# 14-TestFixture.net
KiCad netlist of a schematic drawn in Altium Designer
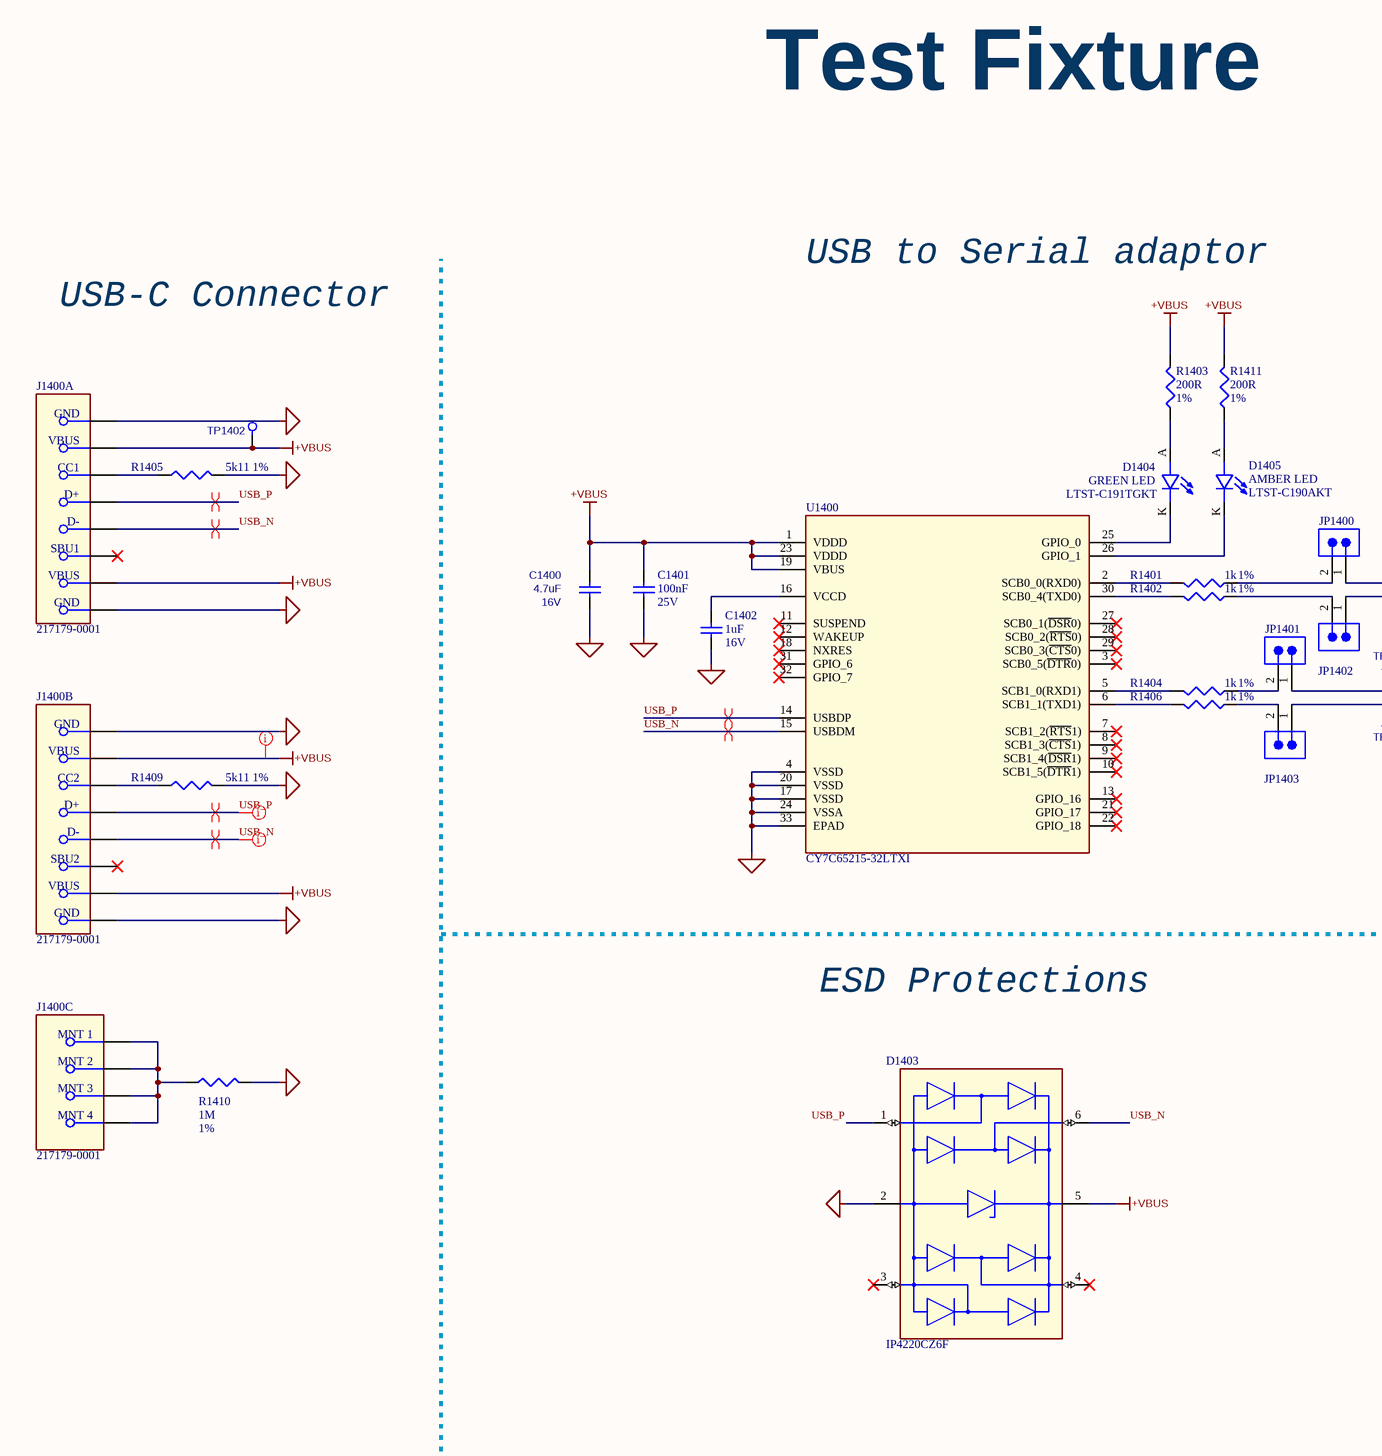
[diagram p0: 14-TestFixture.SchDoc, left]
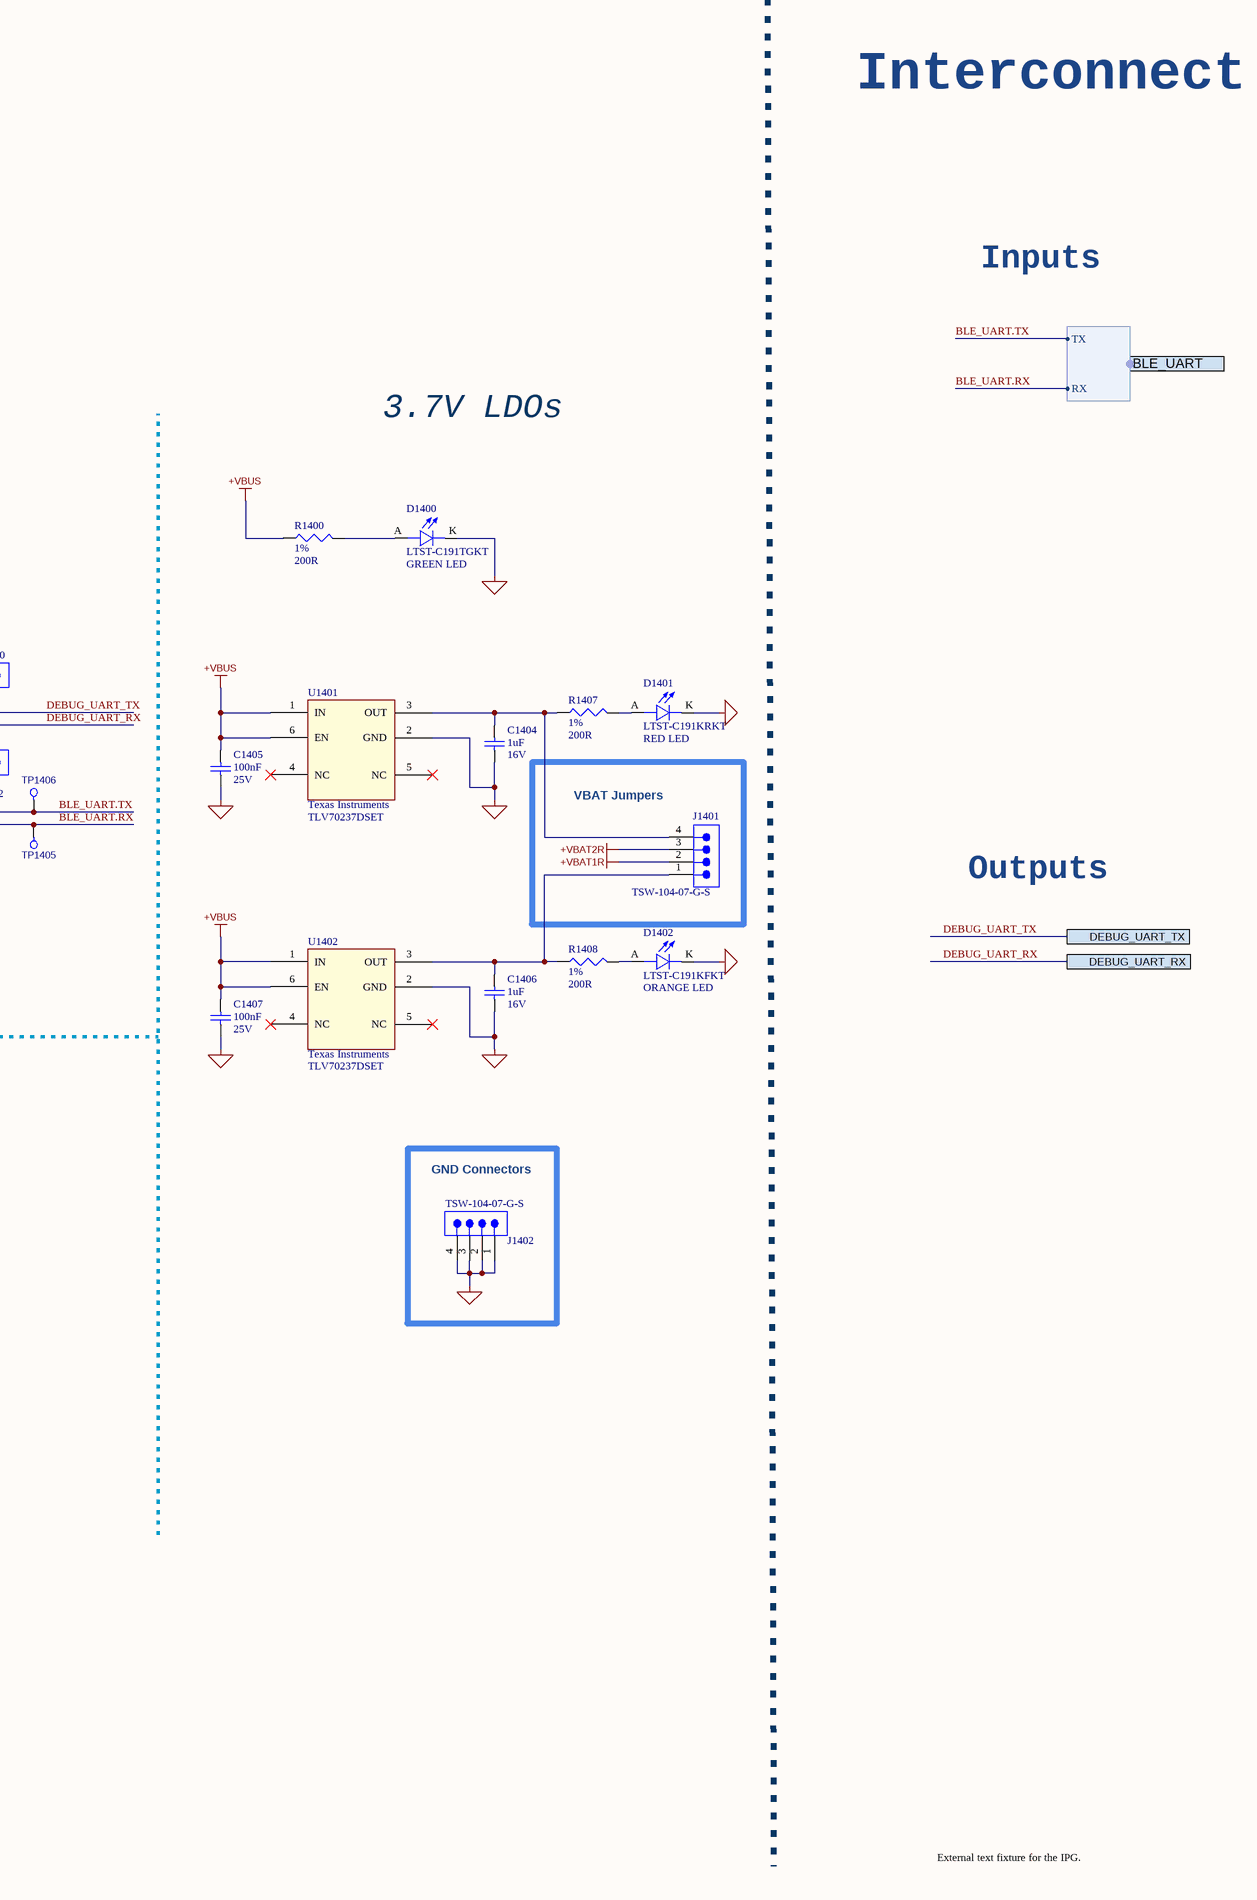
[diagram p1: 14-TestFixture.SchDoc, right]

(export (version "E")
  (design (tool "Eeschema 10.0.6"))
  (components
    (comp (ref "C1400")
      (value "4.7uF")
      (footprint "CAP0603_REDUCED")
      (description "Capacitor, 4.7uF, X5R, 16V, 10%, 0603, Implant-grade")
      (fields
        (field (name "MANUFACTURER") "Murata")
        (field (name "RATING") "16V")
        (field (name "MANUFACTURER PART NUMBER") "GRM188R61C475KE11")
      )
      (libsource (lib "MP-LIBRARY") (part "GRM188R61C475KE11"))
    )
    (comp (ref "C1401")
      (value "100nF")
      (footprint "C0201_C")
      (fields
        (field (name "MANUFACTURER") "Murata")
        (field (name "MANUFACTURER PART NUMBER") "GRM033R61E104KE14J")
        (field (name "RATED DC VOLTAGE (URDC)") "25V")
      )
      (libsource (lib "MP-LIBRARY") (part "GRM033R61E104KE14J"))
    )
    (comp (ref "C1402")
      (value "1uF")
      (footprint "C0201_C")
      (fields
        (field (name "MANUFACTURER") "Murata")
        (field (name "MANUFACTURER PART NUMBER") "GRM033R61C105ME15D")
        (field (name "RATED DC VOLTAGE (URDC)") "16V")
      )
      (libsource (lib "MP-LIBRARY") (part "GRM033R61C105ME15D"))
    )
    (comp (ref "C1404")
      (value "1uF")
      (footprint "C0201_C")
      (fields
        (field (name "MANUFACTURER") "Murata")
        (field (name "MANUFACTURER PART NUMBER") "GRM033R61C105ME15D")
        (field (name "RATED DC VOLTAGE (URDC)") "16V")
      )
      (libsource (lib "MP-LIBRARY") (part "GRM033R61C105ME15D"))
    )
    (comp (ref "C1405")
      (value "100nF")
      (footprint "C0201_C")
      (fields
        (field (name "MANUFACTURER") "Murata")
        (field (name "MANUFACTURER PART NUMBER") "GRM033R61E104KE14J")
        (field (name "RATED DC VOLTAGE (URDC)") "25V")
      )
      (libsource (lib "MP-LIBRARY") (part "GRM033R61E104KE14J"))
    )
    (comp (ref "C1406")
      (value "1uF")
      (footprint "C0201_C")
      (fields
        (field (name "MANUFACTURER") "Murata")
        (field (name "MANUFACTURER PART NUMBER") "GRM033R61C105ME15D")
        (field (name "RATED DC VOLTAGE (URDC)") "16V")
      )
      (libsource (lib "MP-LIBRARY") (part "GRM033R61C105ME15D"))
    )
    (comp (ref "C1407")
      (value "100nF")
      (footprint "C0201_C")
      (fields
        (field (name "MANUFACTURER") "Murata")
        (field (name "MANUFACTURER PART NUMBER") "GRM033R61E104KE14J")
        (field (name "RATED DC VOLTAGE (URDC)") "25V")
      )
      (libsource (lib "MP-LIBRARY") (part "GRM033R61E104KE14J"))
    )
    (comp (ref "D1400")
      (value "LTST-C191TGKT")
      (footprint "LEDC0603")
      (description "LED, GREEN, SMD, 0603, 3.2V, 20mA")
      (fields (field (name "MANUFACTURER") "Lite-On Inc.") (field (name "ALTIUM_VALUE") "GREEN LED"))
      (libsource (lib "MP-LIBRARY") (part "LED GREEN CLEAR SMD 0603"))
    )
    (comp (ref "D1401")
      (value "LTST-C191KRKT")
      (footprint "LEDC0603")
      (description "LED, RED, SMD, 0603, 2V, 30mA")
      (fields (field (name "MANUFACTURER") "Lite-On Inc.") (field (name "ALTIUM_VALUE") "RED LED"))
      (libsource (lib "MP-LIBRARY") (part "LED RED CLEAR SMD 0603"))
    )
    (comp (ref "D1402")
      (value "LTST-C191KFKT")
      (footprint "LEDC0603")
      (description "LED, ORANGE, SMD, 0603, 2V, 30mA")
      (fields (field (name "MANUFACTURER") "Lite-On Inc.") (field (name "ALTIUM_VALUE") "ORANGE LED"))
      (libsource (lib "MP-LIBRARY") (part "LED ORANGE CLEAR SMD 0603"))
    )
    (comp (ref "D1403")
      (value "IP4220CZ6F")
      (footprint "FP-SOT457-IPC_A")
      (description "TVS DIODE 5.5VWM 6TSOP")
      (fields (field (name "MANUFACTURER") "Nexperia"))
      (libsource (lib "MP-LIBRARY") (part "IP4220CZ6F"))
    )
    (comp (ref "D1404")
      (value "LTST-C191TGKT")
      (footprint "LEDC0603")
      (description "LED, GREEN, SMD, 0603, 3.2V, 20mA")
      (fields (field (name "MANUFACTURER") "Lite-On Inc.") (field (name "ALTIUM_VALUE") "GREEN LED"))
      (libsource (lib "") (part "LED GREEN CLEAR SMD 0603_1"))
    )
    (comp (ref "D1405")
      (value "LTST-C190AKT")
      (footprint "LEDC0603")
      (description "LED, Amber, SMD, 0603, 2.1 V, 30 mA")
      (fields (field (name "MANUFACTURER") "Lite-On") (field (name "ALTIUM_VALUE") "AMBER LED"))
      (libsource (lib "MP-LIBRARY") (part "LTST-C190AKT"))
    )
    (comp (ref "J1400")
      (value "217179-0001")
      (footprint "217179-0001")
      (description "CONN RCP USB2.0 TYP C 16P SMD RA")
      (fields (field (name "MANUFACTURER") "Molex"))
      (libsource (lib "MP-LIBRARY") (part "217179-0001"))
    )
    (comp (ref "J1401")
      (value "TSW-104-07-G-S")
      (footprint "SMTC-TSW-104-07-X-S")
      (fields (field (name "MANUFACTURER") "Samtec") (field (name "PARTNUMBER") "TSW-106-07-G-S"))
      (libsource (lib "MP-LIBRARY") (part "TSW-104-07-G-S"))
    )
    (comp (ref "J1402")
      (value "TSW-104-07-G-S")
      (footprint "SMTC-TSW-104-07-X-S")
      (fields (field (name "MANUFACTURER") "Samtec") (field (name "PARTNUMBER") "TSW-106-07-G-S"))
      (libsource (lib "MP-LIBRARY") (part "TSW-104-07-G-S"))
    )
    (comp (ref "JP1400")
      (value "TSW-102-26-G-S")
      (footprint "SMTC-TSW-102-26-XX-S")
      (description "Conn Unshrouded Header HDR 2 POS 2.54mm Solder ST Thru-Hole")
      (fields (field (name "MANUFACTURER") "Samtec"))
      (libsource (lib "MP-LIBRARY") (part "TSW-102-26-G-S"))
    )
    (comp (ref "JP1401")
      (value "TSW-102-26-G-S")
      (footprint "SMTC-TSW-102-26-XX-S")
      (description "Conn Unshrouded Header HDR 2 POS 2.54mm Solder ST Thru-Hole")
      (fields (field (name "MANUFACTURER") "Samtec"))
      (libsource (lib "MP-LIBRARY") (part "TSW-102-26-G-S"))
    )
    (comp (ref "JP1402")
      (value "TSW-102-26-G-S")
      (footprint "SMTC-TSW-102-26-XX-S")
      (description "Conn Unshrouded Header HDR 2 POS 2.54mm Solder ST Thru-Hole")
      (fields (field (name "MANUFACTURER") "Samtec"))
      (libsource (lib "MP-LIBRARY") (part "TSW-102-26-G-S"))
    )
    (comp (ref "JP1403")
      (value "TSW-102-26-G-S")
      (footprint "SMTC-TSW-102-26-XX-S")
      (description "Conn Unshrouded Header HDR 2 POS 2.54mm Solder ST Thru-Hole")
      (fields (field (name "MANUFACTURER") "Samtec"))
      (libsource (lib "MP-LIBRARY") (part "TSW-102-26-G-S"))
    )
    (comp (ref "R1400")
      (value "200R")
      (footprint "RES0402_REDUCED")
      (description "Resistor 200 1%, 0402, Non Implant-grade")
      (fields
        (field (name "POWER") "200 mW")
        (field (name "MANUFACTURER") "Vishay")
        (field (name "TOLERANCE") "1%")
      )
      (libsource (lib "MP-LIBRARY") (part "CRCW0402200RFKEDHP"))
    )
    (comp (ref "R1401")
      (value "1k")
      (footprint "R0201_C")
      (fields
        (field (name "MANUFACTURER") "Vishay")
        (field (name "MANUFACTURER PART NUMBER") "CRCW02011K00FNED")
        (field (name "TOLERANCE") "1%")
        (field (name "POWER") "50mW")
      )
      (libsource (lib "MP-LIBRARY") (part "CRCW02011K00FNED"))
    )
    (comp (ref "R1402")
      (value "1k")
      (footprint "R0201_C")
      (fields
        (field (name "MANUFACTURER") "Vishay")
        (field (name "MANUFACTURER PART NUMBER") "CRCW02011K00FNED")
        (field (name "TOLERANCE") "1%")
        (field (name "POWER") "50mW")
      )
      (libsource (lib "MP-LIBRARY") (part "CRCW02011K00FNED"))
    )
    (comp (ref "R1403")
      (value "200R")
      (footprint "RES0402_REDUCED")
      (description "Resistor 200 1%, 0402, Non Implant-grade")
      (fields
        (field (name "POWER") "200 mW")
        (field (name "MANUFACTURER") "Vishay")
        (field (name "TOLERANCE") "1%")
      )
      (libsource (lib "MP-LIBRARY") (part "CRCW0402200RFKEDHP"))
    )
    (comp (ref "R1404")
      (value "1k")
      (footprint "R0201_C")
      (fields
        (field (name "MANUFACTURER") "Vishay")
        (field (name "MANUFACTURER PART NUMBER") "CRCW02011K00FNED")
        (field (name "TOLERANCE") "1%")
        (field (name "POWER") "50mW")
      )
      (libsource (lib "MP-LIBRARY") (part "CRCW02011K00FNED"))
    )
    (comp (ref "R1405")
      (value "5k11")
      (footprint "R0201_C")
      (fields
        (field (name "TOLERANCE") "1%")
        (field (name "MANUFACTURER") "Vishay")
        (field (name "MANUFACTURER PART NUMBER") "CRCW02015K11FNED")
        (field (name "POWER") "50mW")
      )
      (libsource (lib "MP-LIBRARY") (part "CRCW02015K11FNED"))
    )
    (comp (ref "R1406")
      (value "1k")
      (footprint "R0201_C")
      (fields
        (field (name "MANUFACTURER") "Vishay")
        (field (name "MANUFACTURER PART NUMBER") "CRCW02011K00FNED")
        (field (name "TOLERANCE") "1%")
        (field (name "POWER") "50mW")
      )
      (libsource (lib "MP-LIBRARY") (part "CRCW02011K00FNED"))
    )
    (comp (ref "R1407")
      (value "200R")
      (footprint "RES0402_REDUCED")
      (description "Resistor 200 1%, 0402, Non Implant-grade")
      (fields
        (field (name "POWER") "200 mW")
        (field (name "MANUFACTURER") "Vishay")
        (field (name "TOLERANCE") "1%")
      )
      (libsource (lib "MP-LIBRARY") (part "CRCW0402200RFKEDHP"))
    )
    (comp (ref "R1408")
      (value "200R")
      (footprint "RES0402_REDUCED")
      (description "Resistor 200 1%, 0402, Non Implant-grade")
      (fields
        (field (name "POWER") "200 mW")
        (field (name "MANUFACTURER") "Vishay")
        (field (name "TOLERANCE") "1%")
      )
      (libsource (lib "MP-LIBRARY") (part "CRCW0402200RFKEDHP"))
    )
    (comp (ref "R1409")
      (value "5k11")
      (footprint "R0201_C")
      (fields
        (field (name "TOLERANCE") "1%")
        (field (name "MANUFACTURER") "Vishay")
        (field (name "MANUFACTURER PART NUMBER") "CRCW02015K11FNED")
        (field (name "POWER") "50mW")
      )
      (libsource (lib "MP-LIBRARY") (part "CRCW02015K11FNED"))
    )
    (comp (ref "R1410")
      (value "1M")
      (footprint "R0201_C")
      (fields
        (field (name "MANUFACTURER") "Vishay")
        (field (name "MANUFACTURER PART NUMBER") "CRCW02011M00FNED")
        (field (name "TOLERANCE") "1%")
        (field (name "POWER") "50mW")
      )
      (libsource (lib "MP-LIBRARY") (part "CRCW02011M00FNED"))
    )
    (comp (ref "R1411")
      (value "200R")
      (footprint "RES0402_REDUCED")
      (description "Resistor 200 1%, 0402, Non Implant-grade")
      (fields
        (field (name "POWER") "200 mW")
        (field (name "MANUFACTURER") "Vishay")
        (field (name "TOLERANCE") "1%")
      )
      (libsource (lib "MP-LIBRARY") (part "CRCW0402200RFKEDHP"))
    )
    (comp (ref "TP1402")
      (value "Test Point")
      (footprint "testpad_0.9mm")
      (description "Test pad, 0.90mm circular pad")
      (libsource (lib "MP-LIBRARY") (part "Test Point"))
    )
    (comp (ref "TP1405")
      (value "Test Point")
      (footprint "testpad_0.9mm")
      (description "Test pad, 0.90mm circular pad")
      (libsource (lib "MP-LIBRARY") (part "Test Point"))
    )
    (comp (ref "TP1406")
      (value "Test Point")
      (footprint "testpad_0.9mm")
      (description "Test pad, 0.90mm circular pad")
      (libsource (lib "MP-LIBRARY") (part "Test Point"))
    )
    (comp (ref "U1400")
      (value "CY7C65215-32LTXI")
      (footprint "PG-VQFN-32-803")
      (description "IC USB TO SERIAL BRIDGE 32QFN")
      (fields (field (name "MANUFACTURER") "Infineon"))
      (libsource (lib "MP-LIBRARY") (part "CY7C65215-32LTXI"))
    )
    (comp (ref "U1401")
      (value "TLV70237DSET")
      (footprint "SON127P600-8N")
      (description "Fixed Positive LDO Regulator, 3.7V, 0.375V Dropout, PDSO6")
      (fields
        (field (name "MANUFACTURER") "Texas Instruments")
        (field (name "MANUFACTURER PART NUMBER") "TLV70237DSET")
      )
      (libsource (lib "MP-LIBRARY") (part "TLV70237DSET"))
    )
    (comp (ref "U1402")
      (value "TLV70237DSET")
      (footprint "SON127P600-8N")
      (description "Fixed Positive LDO Regulator, 3.7V, 0.375V Dropout, PDSO6")
      (fields
        (field (name "MANUFACTURER") "Texas Instruments")
        (field (name "MANUFACTURER PART NUMBER") "TLV70237DSET")
      )
      (libsource (lib "MP-LIBRARY") (part "TLV70237DSET"))
    )
  )
  (nets
    (net (code "2") (name "+VBAT1R") (class "Default")
      (node (ref "J1401") (pin "2") (pinfunction "2_2") (pintype "passive"))
    )
    (net (code "3") (name "+VBAT2R") (class "Default")
      (node (ref "J1401") (pin "3") (pinfunction "3_3") (pintype "passive"))
    )
    (net (code "4") (name "+VBUS") (class "Default")
      (node (ref "C1400") (pin "1") (pinfunction "1_1") (pintype "passive"))
      (node (ref "C1401") (pin "2") (pinfunction "2_2") (pintype "passive"))
      (node (ref "C1405") (pin "2") (pinfunction "2_2") (pintype "passive"))
      (node (ref "C1407") (pin "2") (pinfunction "2_2") (pintype "passive"))
      (node (ref "D1403") (pin "5") (pinfunction "VP_5") (pintype "power_in"))
      (node (ref "J1400") (pin "A4") (pinfunction "VBUS_A4") (pintype "passive"))
      (node (ref "J1400") (pin "A9") (pinfunction "VBUS_A9") (pintype "passive"))
      (node (ref "J1400") (pin "B4") (pinfunction "VBUS_B4") (pintype "passive"))
      (node (ref "J1400") (pin "B9") (pinfunction "VBUS_B9") (pintype "passive"))
      (node (ref "R1400") (pin "1") (pinfunction "1_1") (pintype "passive"))
      (node (ref "R1403") (pin "2") (pinfunction "2_2") (pintype "passive"))
      (node (ref "R1411") (pin "2") (pinfunction "2_2") (pintype "passive"))
      (node (ref "TP1402") (pin "1") (pinfunction "1_1") (pintype "passive"))
      (node (ref "U1400") (pin "1") (pinfunction "VDDD_1") (pintype "passive"))
      (node (ref "U1400") (pin "19") (pinfunction "VBUS_19") (pintype "passive"))
      (node (ref "U1400") (pin "23") (pinfunction "VDDD_23") (pintype "passive"))
      (node (ref "U1401") (pin "1") (pinfunction "IN_1") (pintype "passive"))
      (node (ref "U1401") (pin "6") (pinfunction "EN_6") (pintype "passive"))
      (node (ref "U1402") (pin "1") (pinfunction "IN_1") (pintype "passive"))
      (node (ref "U1402") (pin "6") (pinfunction "EN_6") (pintype "passive"))
    )
    (net (code "5") (name "/BLE_UART.RX") (class "Default")
      (node (ref "JP1403") (pin "1") (pinfunction "1_1") (pintype "passive"))
      (node (ref "TP1405") (pin "1") (pinfunction "1_1") (pintype "passive"))
    )
    (net (code "6") (name "/BLE_UART.TX") (class "Default")
      (node (ref "JP1401") (pin "1") (pinfunction "1_1") (pintype "passive"))
      (node (ref "TP1406") (pin "1") (pinfunction "1_1") (pintype "passive"))
    )
    (net (code "7") (name "/DEBUG_UART_RX") (class "Default")
      (node (ref "JP1402") (pin "1") (pinfunction "1_1") (pintype "passive"))
    )
    (net (code "8") (name "/DEBUG_UART_TX") (class "Default")
      (node (ref "JP1400") (pin "1") (pinfunction "1_1") (pintype "passive"))
    )
    (net (code "9") (name "/USB_N") (class "Default")
      (node (ref "D1403") (pin "6") (pinfunction "I/O4_6") (pintype "bidirectional"))
      (node (ref "J1400") (pin "A7") (pinfunction "D-_A7") (pintype "passive"))
      (node (ref "J1400") (pin "B7") (pinfunction "D-_B7") (pintype "passive"))
      (node (ref "U1400") (pin "15") (pinfunction "USBDM_15") (pintype "passive"))
    )
    (net (code "10") (name "/USB_P") (class "Default")
      (node (ref "D1403") (pin "1") (pinfunction "I/O1_1") (pintype "bidirectional"))
      (node (ref "J1400") (pin "A6") (pinfunction "D+_A6") (pintype "passive"))
      (node (ref "J1400") (pin "B6") (pinfunction "D+_B6") (pintype "passive"))
      (node (ref "U1400") (pin "14") (pinfunction "USBDP_14") (pintype "passive"))
    )
    (net (code "12") (name "GND") (class "Default")
      (node (ref "C1400") (pin "2") (pinfunction "2_2") (pintype "passive"))
      (node (ref "C1401") (pin "1") (pinfunction "1_1") (pintype "passive"))
      (node (ref "C1402") (pin "1") (pinfunction "1_1") (pintype "passive"))
      (node (ref "C1404") (pin "2") (pinfunction "2_2") (pintype "passive"))
      (node (ref "C1405") (pin "1") (pinfunction "1_1") (pintype "passive"))
      (node (ref "C1406") (pin "1") (pinfunction "1_1") (pintype "passive"))
      (node (ref "C1407") (pin "1") (pinfunction "1_1") (pintype "passive"))
      (node (ref "D1400") (pin "K") (pinfunction "K_K") (pintype "passive"))
      (node (ref "D1401") (pin "K") (pinfunction "K_K") (pintype "passive"))
      (node (ref "D1402") (pin "K") (pinfunction "K_K") (pintype "passive"))
      (node (ref "D1403") (pin "2") (pinfunction "GND_2") (pintype "power_in"))
      (node (ref "J1400") (pin "A1") (pinfunction "GND_A1") (pintype "passive"))
      (node (ref "J1400") (pin "A12") (pinfunction "GND_A12") (pintype "passive"))
      (node (ref "J1400") (pin "B1") (pinfunction "GND_B1") (pintype "passive"))
      (node (ref "J1400") (pin "B12") (pinfunction "GND_B12") (pintype "passive"))
      (node (ref "J1402") (pin "1") (pinfunction "1_1") (pintype "passive"))
      (node (ref "J1402") (pin "2") (pinfunction "2_2") (pintype "passive"))
      (node (ref "J1402") (pin "3") (pinfunction "3_3") (pintype "passive"))
      (node (ref "J1402") (pin "4") (pinfunction "4_4") (pintype "passive"))
      (node (ref "R1405") (pin "2") (pinfunction "2_2") (pintype "passive"))
      (node (ref "R1409") (pin "2") (pinfunction "2_2") (pintype "passive"))
      (node (ref "R1410") (pin "2") (pinfunction "2_2") (pintype "passive"))
      (node (ref "U1400") (pin "17") (pinfunction "VSSD_17") (pintype "passive"))
      (node (ref "U1400") (pin "20") (pinfunction "VSSD_20") (pintype "passive"))
      (node (ref "U1400") (pin "24") (pinfunction "VSSA_24") (pintype "passive"))
      (node (ref "U1400") (pin "33") (pinfunction "EPAD_33") (pintype "passive"))
      (node (ref "U1400") (pin "4") (pinfunction "VSSD_4") (pintype "passive"))
      (node (ref "U1401") (pin "2") (pinfunction "GND_2") (pintype "passive"))
      (node (ref "U1402") (pin "2") (pinfunction "GND_2") (pintype "passive"))
    )
    (net (code "13") (name "Net-(D1400-PadA)") (class "Default")
      (node (ref "D1400") (pin "A") (pinfunction "A_A") (pintype "passive"))
      (node (ref "R1400") (pin "2") (pinfunction "2_2") (pintype "passive"))
    )
    (net (code "14") (name "Net-(D1401-PadA)") (class "Default")
      (node (ref "D1401") (pin "A") (pinfunction "A_A") (pintype "passive"))
      (node (ref "R1407") (pin "2") (pinfunction "2_2") (pintype "passive"))
    )
    (net (code "15") (name "Net-(D1402-PadA)") (class "Default")
      (node (ref "D1402") (pin "A") (pinfunction "A_A") (pintype "passive"))
      (node (ref "R1408") (pin "2") (pinfunction "2_2") (pintype "passive"))
    )
    (net (code "16") (name "Net-(D1404-PadA)") (class "Default")
      (node (ref "D1404") (pin "A") (pinfunction "A_A") (pintype "passive"))
      (node (ref "R1403") (pin "1") (pinfunction "1_1") (pintype "passive"))
    )
    (net (code "17") (name "Net-(D1405-PadA)") (class "Default")
      (node (ref "D1405") (pin "A") (pinfunction "A_A") (pintype "passive"))
      (node (ref "R1411") (pin "1") (pinfunction "1_1") (pintype "passive"))
    )
    (net (code "18") (name "Net-(J1400A-CC1)") (class "Default")
      (node (ref "J1400") (pin "A5") (pinfunction "CC1_A5") (pintype "passive"))
      (node (ref "R1405") (pin "1") (pinfunction "1_1") (pintype "passive"))
    )
    (net (code "19") (name "Net-(J1400B-CC2)") (class "Default")
      (node (ref "J1400") (pin "B5") (pinfunction "CC2_B5") (pintype "passive"))
      (node (ref "R1409") (pin "1") (pinfunction "1_1") (pintype "passive"))
    )
    (net (code "20") (name "Net-(J1400C-MNT_1)") (class "Default")
      (node (ref "J1400") (pin "1") (pinfunction "MNT_1_1") (pintype "passive"))
      (node (ref "J1400") (pin "2") (pinfunction "MNT_2_2") (pintype "passive"))
      (node (ref "J1400") (pin "3") (pinfunction "MNT_3_3") (pintype "passive"))
      (node (ref "J1400") (pin "4") (pinfunction "MNT_4_4") (pintype "passive"))
      (node (ref "R1410") (pin "1") (pinfunction "1_1") (pintype "passive"))
    )
    (net (code "21") (name "Net-(JP1400-Pad2)") (class "Default")
      (node (ref "JP1400") (pin "2") (pinfunction "2_2") (pintype "passive"))
      (node (ref "R1401") (pin "1") (pinfunction "1_1") (pintype "passive"))
    )
    (net (code "22") (name "Net-(JP1401-Pad2)") (class "Default")
      (node (ref "JP1401") (pin "2") (pinfunction "2_2") (pintype "passive"))
      (node (ref "R1404") (pin "1") (pinfunction "1_1") (pintype "passive"))
    )
    (net (code "23") (name "Net-(JP1402-Pad2)") (class "Default")
      (node (ref "JP1402") (pin "2") (pinfunction "2_2") (pintype "passive"))
      (node (ref "R1402") (pin "1") (pinfunction "1_1") (pintype "passive"))
    )
    (net (code "24") (name "Net-(JP1403-Pad2)") (class "Default")
      (node (ref "JP1403") (pin "2") (pinfunction "2_2") (pintype "passive"))
      (node (ref "R1406") (pin "1") (pinfunction "1_1") (pintype "passive"))
    )
    (net (code "25") (name "Net-(U1400-GPIO_0)") (class "Default")
      (node (ref "D1404") (pin "K") (pinfunction "K_K") (pintype "passive"))
      (node (ref "U1400") (pin "25") (pinfunction "GPIO_0_25") (pintype "passive"))
    )
    (net (code "26") (name "Net-(U1400-GPIO_1)") (class "Default")
      (node (ref "D1405") (pin "K") (pinfunction "K_K") (pintype "passive"))
      (node (ref "U1400") (pin "26") (pinfunction "GPIO_1_26") (pintype "passive"))
    )
    (net (code "27") (name "Net-(U1400-SCB0_0(RXD0))") (class "Default")
      (node (ref "R1401") (pin "2") (pinfunction "2_2") (pintype "passive"))
      (node (ref "U1400") (pin "2") (pinfunction "SCB0_0(RXD0)_2") (pintype "passive"))
    )
    (net (code "28") (name "Net-(U1400-SCB0_4(TXD0))") (class "Default")
      (node (ref "R1402") (pin "2") (pinfunction "2_2") (pintype "passive"))
      (node (ref "U1400") (pin "30") (pinfunction "SCB0_4(TXD0)_30") (pintype "passive"))
    )
    (net (code "29") (name "Net-(U1400-SCB1_0(RXD1))") (class "Default")
      (node (ref "R1404") (pin "2") (pinfunction "2_2") (pintype "passive"))
      (node (ref "U1400") (pin "5") (pinfunction "SCB1_0(RXD1)_5") (pintype "passive"))
    )
    (net (code "30") (name "Net-(U1400-SCB1_1(TXD1))") (class "Default")
      (node (ref "R1406") (pin "2") (pinfunction "2_2") (pintype "passive"))
      (node (ref "U1400") (pin "6") (pinfunction "SCB1_1(TXD1)_6") (pintype "passive"))
    )
    (net (code "31") (name "Net-(U1400-VCCD)") (class "Default")
      (node (ref "C1402") (pin "2") (pinfunction "2_2") (pintype "passive"))
      (node (ref "U1400") (pin "16") (pinfunction "VCCD_16") (pintype "passive"))
    )
    (net (code "32") (name "Net-(U1401-OUT)") (class "Default")
      (node (ref "C1404") (pin "1") (pinfunction "1_1") (pintype "passive"))
      (node (ref "J1401") (pin "4") (pinfunction "4_4") (pintype "passive"))
      (node (ref "R1407") (pin "1") (pinfunction "1_1") (pintype "passive"))
      (node (ref "U1401") (pin "3") (pinfunction "OUT_3") (pintype "passive"))
    )
    (net (code "33") (name "Net-(U1402-OUT)") (class "Default")
      (node (ref "C1406") (pin "2") (pinfunction "2_2") (pintype "passive"))
      (node (ref "J1401") (pin "1") (pinfunction "1_1") (pintype "passive"))
      (node (ref "R1408") (pin "1") (pinfunction "1_1") (pintype "passive"))
      (node (ref "U1402") (pin "3") (pinfunction "OUT_3") (pintype "passive"))
    )
    (net (code "34") (name "unconnected-(D1403-I{slash}O2-Pad3)") (class "Default")
      (node (ref "D1403") (pin "3") (pinfunction "I/O2_3") (pintype "bidirectional+no_connect"))
    )
    (net (code "35") (name "unconnected-(D1403-I{slash}O3-Pad4)") (class "Default")
      (node (ref "D1403") (pin "4") (pinfunction "I/O3_4") (pintype "bidirectional+no_connect"))
    )
    (net (code "36") (name "unconnected-(J1400A-SBU1-PadA8)") (class "Default")
      (node (ref "J1400") (pin "A8") (pinfunction "SBU1_A8") (pintype "passive+no_connect"))
    )
    (net (code "37") (name "unconnected-(J1400B-SBU2-PadB8)") (class "Default")
      (node (ref "J1400") (pin "B8") (pinfunction "SBU2_B8") (pintype "passive+no_connect"))
    )
    (net (code "38") (name "unconnected-(U1400-GPIO_6-Pad31)") (class "Default")
      (node (ref "U1400") (pin "31") (pinfunction "GPIO_6_31") (pintype "passive+no_connect"))
    )
    (net (code "39") (name "unconnected-(U1400-GPIO_7-Pad32)") (class "Default")
      (node (ref "U1400") (pin "32") (pinfunction "GPIO_7_32") (pintype "passive+no_connect"))
    )
    (net (code "40") (name "unconnected-(U1400-GPIO_16-Pad13)") (class "Default")
      (node (ref "U1400") (pin "13") (pinfunction "GPIO_16_13") (pintype "passive+no_connect"))
    )
    (net (code "41") (name "unconnected-(U1400-GPIO_17-Pad21)") (class "Default")
      (node (ref "U1400") (pin "21") (pinfunction "GPIO_17_21") (pintype "passive+no_connect"))
    )
    (net (code "42") (name "unconnected-(U1400-GPIO_18-Pad22)") (class "Default")
      (node (ref "U1400") (pin "22") (pinfunction "GPIO_18_22") (pintype "passive+no_connect"))
    )
    (net (code "43") (name "unconnected-(U1400-NXRES-Pad18)") (class "Default")
      (node (ref "U1400") (pin "18") (pinfunction "NXRES_18") (pintype "passive+no_connect"))
    )
    (net (code "44") (name "unconnected-(U1400-SCB0_1(~{DSR}0)-Pad27)") (class "Default")
      (node (ref "U1400") (pin "27") (pinfunction "SCB0_1(~{DSR}0)_27") (pintype "passive+no_connect"))
    )
    (net (code "45") (name "unconnected-(U1400-SCB0_2(~{RTS}0)-Pad28)") (class "Default")
      (node (ref "U1400") (pin "28") (pinfunction "SCB0_2(~{RTS}0)_28") (pintype "passive+no_connect"))
    )
    (net (code "46") (name "unconnected-(U1400-SCB0_3(~{CTS}0)-Pad29)") (class "Default")
      (node (ref "U1400") (pin "29") (pinfunction "SCB0_3(~{CTS}0)_29") (pintype "passive+no_connect"))
    )
    (net (code "47") (name "unconnected-(U1400-SCB0_5(~{DTR}0)-Pad3)") (class "Default")
      (node (ref "U1400") (pin "3") (pinfunction "SCB0_5(~{DTR}0)_3") (pintype "passive+no_connect"))
    )
    (net (code "48") (name "unconnected-(U1400-SCB1_2(~{RTS}1)-Pad7)") (class "Default")
      (node (ref "U1400") (pin "7") (pinfunction "SCB1_2(~{RTS}1)_7") (pintype "passive+no_connect"))
    )
    (net (code "49") (name "unconnected-(U1400-SCB1_3(~{CTS}1)-Pad8)") (class "Default")
      (node (ref "U1400") (pin "8") (pinfunction "SCB1_3(~{CTS}1)_8") (pintype "passive+no_connect"))
    )
    (net (code "50") (name "unconnected-(U1400-SCB1_4(~{DSR}1)-Pad9)") (class "Default")
      (node (ref "U1400") (pin "9") (pinfunction "SCB1_4(~{DSR}1)_9") (pintype "passive+no_connect"))
    )
    (net (code "51") (name "unconnected-(U1400-SCB1_5(~{DTR}1)-Pad10)") (class "Default")
      (node (ref "U1400") (pin "10") (pinfunction "SCB1_5(~{DTR}1)_10") (pintype "passive+no_connect"))
    )
    (net (code "52") (name "unconnected-(U1400-SUSPEND-Pad11)") (class "Default")
      (node (ref "U1400") (pin "11") (pinfunction "SUSPEND_11") (pintype "passive+no_connect"))
    )
    (net (code "53") (name "unconnected-(U1400-WAKEUP-Pad12)") (class "Default")
      (node (ref "U1400") (pin "12") (pinfunction "WAKEUP_12") (pintype "passive+no_connect"))
    )
    (net (code "54") (name "unconnected-(U1401-NC-Pad4)") (class "Default")
      (node (ref "U1401") (pin "4") (pinfunction "NC_4") (pintype "passive+no_connect"))
    )
    (net (code "55") (name "unconnected-(U1401-NC-Pad5)") (class "Default")
      (node (ref "U1401") (pin "5") (pinfunction "NC_5") (pintype "passive+no_connect"))
    )
    (net (code "56") (name "unconnected-(U1402-NC-Pad4)") (class "Default")
      (node (ref "U1402") (pin "4") (pinfunction "NC_4") (pintype "passive+no_connect"))
    )
    (net (code "57") (name "unconnected-(U1402-NC-Pad5)") (class "Default")
      (node (ref "U1402") (pin "5") (pinfunction "NC_5") (pintype "passive+no_connect"))
    )
  )
)
